# Power.net
KiCad netlist of a schematic drawn in Altium Designer
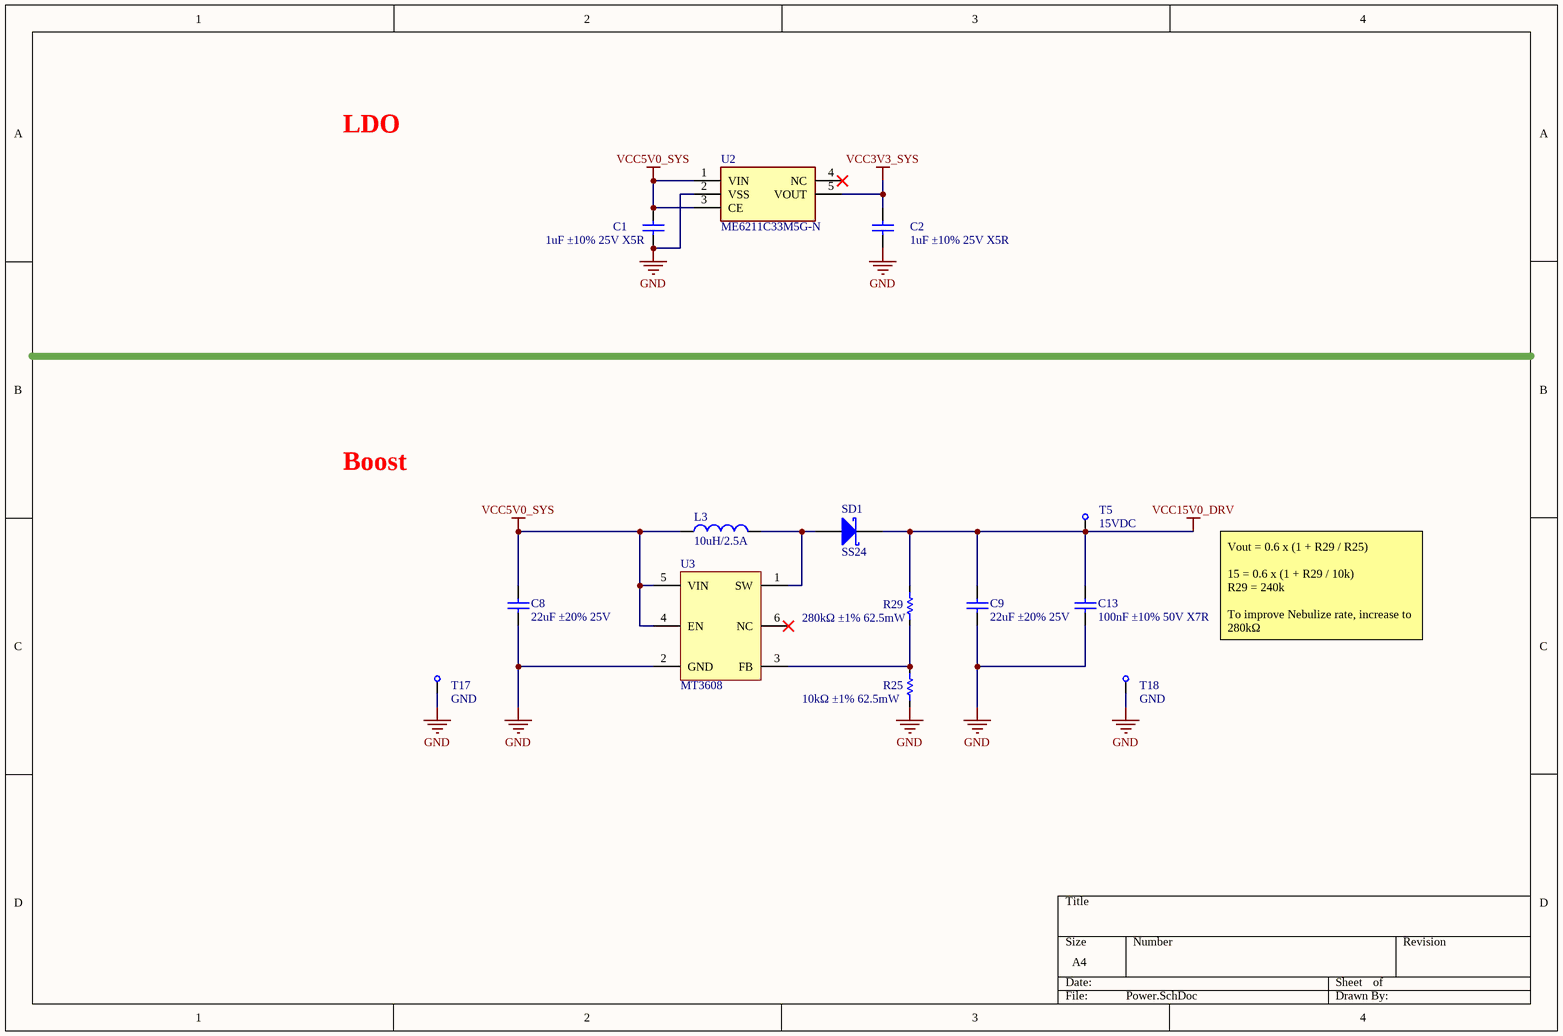
[diagram p0: Power.SchDoc]

(export (version "E")
  (design (tool "Eeschema 10.0.6"))
  (components
    (comp (ref "C1")
      (value "1uF ±10% 25V X5R")
      (footprint "C0402")
      (description "CL05A475KP5NRNC")
      (fields (field (name "PUBLISHER") "Altium Limited"))
      (libsource (lib "Component") (part "Cap"))
    )
    (comp (ref "C2")
      (value "1uF ±10% 25V X5R")
      (footprint "C0402")
      (description "CL05A475KP5NRNC")
      (fields (field (name "PUBLISHER") "Altium Limited"))
      (libsource (lib "Component") (part "Cap"))
    )
    (comp (ref "C8")
      (value "22uF ±20% 25V")
      (footprint "C0805")
      (description "CL21A226MAQNNNE")
      (fields (field (name "PUBLISHER") "Altium Limited"))
      (libsource (lib "Component") (part "C0805"))
    )
    (comp (ref "C9")
      (value "22uF ±20% 25V")
      (footprint "C0805")
      (description "CL21A226MAQNNNE")
      (fields (field (name "PUBLISHER") "Altium Limited"))
      (libsource (lib "Component") (part "C0805"))
    )
    (comp (ref "C13")
      (value "100nF ±10% 50V X7R")
      (footprint "C0402")
      (description "CL05B104KB54PNC")
      (fields (field (name "PUBLISHER") "Altium Limited"))
      (libsource (lib "Miscellaneous Devices") (part "Cap Semi"))
    )
    (comp (ref "L3")
      (value "10uH/2.5A")
      (footprint "SP0502")
      (description "SWPA6028S100MT")
      (fields (field (name "PUBLISHER") "Altium Limited"))
      (libsource (lib "Miscellaneous Devices") (part "Inductor"))
    )
    (comp (ref "R25")
      (value "10kΩ ±1% 62.5mW")
      (footprint "R0402")
      (description "0402WGF1002TCE")
      (fields (field (name "PUBLISHER") "Altium Limited"))
      (libsource (lib "Component") (part "R0402"))
    )
    (comp (ref "R29")
      (value "280kΩ ±1% 62.5mW")
      (footprint "R0402")
      (description "0402WGF2803TCE")
      (fields (field (name "PUBLISHER") "Altium Limited"))
      (libsource (lib "Component") (part "R0402"))
    )
    (comp (ref "SD1")
      (value "SS24")
      (footprint "SMA-403D")
      (description "C50645")
      (fields (field (name "PUBLISHER") "Altium Limited"))
      (libsource (lib "Miscellaneous Devices") (part "D Schottky"))
    )
    (comp (ref "T5")
      (value "15VDC")
      (footprint "TP-SIP-1-Small1")
      (libsource (lib "others") (part "TP-SIP-1-Small"))
    )
    (comp (ref "T17")
      (value "GND")
      (footprint "TP-SIP-1-Small1")
      (libsource (lib "others") (part "TP-SIP-1-Small"))
    )
    (comp (ref "T18")
      (value "GND")
      (footprint "TP-SIP-1-Small1")
      (libsource (lib "others") (part "TP-SIP-1-Small"))
    )
    (comp (ref "U2")
      (value "ME6211C33M5G-N")
      (footprint "SamacSys:SOT95P270X145-5N")
      (description "ME6211C33M5G-N\r\nLDO 3.3V")
      (libsource (lib "*") (part "ME6211C33M5G-N"))
    )
    (comp (ref "U3")
      (value "MT3608")
      (footprint "SOT95P280X110-6N")
      (libsource (lib "Atomizer_medical") (part "MT3608"))
    )
  )
  (nets
    (net (code "1") (name "GND") (class "Default")
      (node (ref "C1") (pin "1") (pinfunction "1_1") (pintype "passive"))
      (node (ref "C13") (pin "2") (pinfunction "2_2") (pintype "passive"))
      (node (ref "C2") (pin "1") (pinfunction "1_1") (pintype "passive"))
      (node (ref "C8") (pin "1") (pinfunction "1_1") (pintype "passive"))
      (node (ref "C9") (pin "1") (pinfunction "1_1") (pintype "passive"))
      (node (ref "R25") (pin "1") (pinfunction "1_1") (pintype "passive"))
      (node (ref "T17") (pin "1") (pinfunction "1_1") (pintype "passive"))
      (node (ref "T18") (pin "1") (pinfunction "1_1") (pintype "passive"))
      (node (ref "U2") (pin "2") (pinfunction "VSS_2") (pintype "passive"))
      (node (ref "U3") (pin "2") (pinfunction "GND_2") (pintype "passive"))
    )
    (net (code "2") (name "Net-(SD1-A)") (class "Default")
      (node (ref "L3") (pin "2") (pinfunction "2_2") (pintype "passive"))
      (node (ref "SD1") (pin "1") (pinfunction "A_1") (pintype "passive"))
      (node (ref "U3") (pin "1") (pinfunction "SW_1") (pintype "passive"))
    )
    (net (code "3") (name "Net-(U3-FB)") (class "Default")
      (node (ref "R25") (pin "2") (pinfunction "2_2") (pintype "passive"))
      (node (ref "R29") (pin "1") (pinfunction "1_1") (pintype "passive"))
      (node (ref "U3") (pin "3") (pinfunction "FB_3") (pintype "passive"))
    )
    (net (code "4") (name "VCC3V3_SYS") (class "Default")
      (node (ref "C2") (pin "2") (pinfunction "2_2") (pintype "passive"))
      (node (ref "U2") (pin "5") (pinfunction "VOUT_5") (pintype "passive"))
    )
    (net (code "5") (name "VCC5V0_SYS") (class "Default")
      (node (ref "C1") (pin "2") (pinfunction "2_2") (pintype "passive"))
      (node (ref "C8") (pin "2") (pinfunction "2_2") (pintype "passive"))
      (node (ref "L3") (pin "1") (pinfunction "1_1") (pintype "passive"))
      (node (ref "U2") (pin "1") (pinfunction "VIN_1") (pintype "passive"))
      (node (ref "U2") (pin "3") (pinfunction "CE_3") (pintype "passive"))
      (node (ref "U3") (pin "4") (pinfunction "EN_4") (pintype "passive"))
      (node (ref "U3") (pin "5") (pinfunction "VIN_5") (pintype "passive"))
    )
    (net (code "6") (name "VCC15V0_DRV") (class "Default")
      (node (ref "C13") (pin "1") (pinfunction "1_1") (pintype "passive"))
      (node (ref "C9") (pin "2") (pinfunction "2_2") (pintype "passive"))
      (node (ref "R29") (pin "2") (pinfunction "2_2") (pintype "passive"))
      (node (ref "SD1") (pin "2") (pinfunction "K_2") (pintype "passive"))
      (node (ref "T5") (pin "1") (pinfunction "1_1") (pintype "passive"))
    )
    (net (code "7") (name "unconnected-(U2-NC-Pad4)") (class "Default")
      (node (ref "U2") (pin "4") (pinfunction "NC_4") (pintype "passive+no_connect"))
    )
    (net (code "8") (name "unconnected-(U3-NC-Pad6)") (class "Default")
      (node (ref "U3") (pin "6") (pinfunction "NC_6") (pintype "passive+no_connect"))
    )
  )
)
